# control_board_SMD.net
KiCad netlist of a schematic drawn in EAGLE
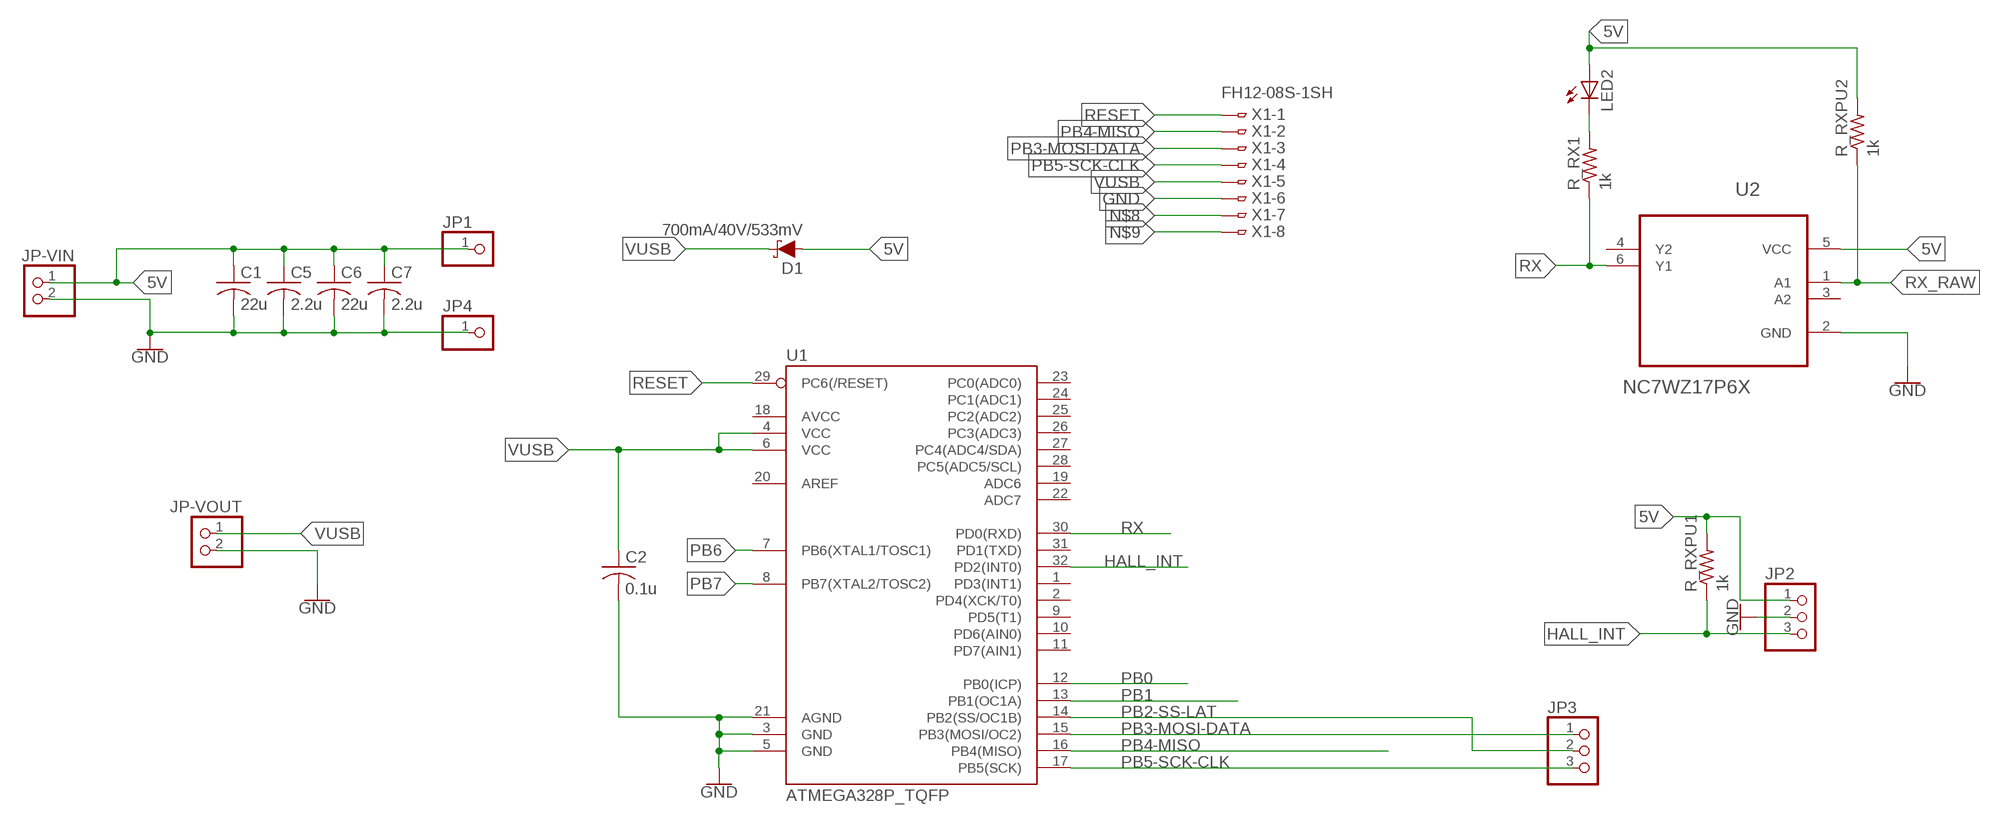
[diagram p0: schematic, sheet 1]

(export (version "E")
  (design (tool "Eeschema 10.0.6"))
  (components
    (comp (ref "C1")
      (value "22u")
      (footprint "eagle-import:C1210")
      (libsource (lib "eagle-import") (part "C-USC1210"))
    )
    (comp (ref "C2")
      (value "0.1u")
      (footprint "eagle-import:C0603")
      (libsource (lib "eagle-import") (part "C-USC0603"))
    )
    (comp (ref "C5")
      (value "2.2u")
      (footprint "eagle-import:C1210")
      (libsource (lib "eagle-import") (part "C-USC1210"))
    )
    (comp (ref "C6")
      (value "22u")
      (footprint "eagle-import:C1210")
      (libsource (lib "eagle-import") (part "C-USC1210"))
    )
    (comp (ref "C7")
      (value "2.2u")
      (footprint "eagle-import:C1210")
      (libsource (lib "eagle-import") (part "C-USC1210"))
    )
    (comp (ref "D1")
      (value "700mA/40V/533mV")
      (footprint "eagle-import:SOT23-3")
      (libsource (lib "eagle-import") (part "DIODE-SCHOTTKY-ZLLS500"))
    )
    (comp (ref "JP-VIN")
      (value "PINHD-1X2")
      (footprint "eagle-import:1X02")
      (libsource (lib "eagle-import") (part "PINHD-1X2"))
    )
    (comp (ref "JP-VOUT")
      (value "PINHD-1X2")
      (footprint "eagle-import:1X02")
      (libsource (lib "eagle-import") (part "PINHD-1X2"))
    )
    (comp (ref "JP1")
      (value "PINHD-1X1")
      (footprint "eagle-import:1X01")
      (libsource (lib "eagle-import") (part "PINHD-1X1"))
    )
    (comp (ref "JP2")
      (value "PINHD-1X3")
      (footprint "eagle-import:1X03")
      (libsource (lib "eagle-import") (part "PINHD-1X3"))
    )
    (comp (ref "JP3")
      (value "PINHD-1X3")
      (footprint "eagle-import:1X03")
      (libsource (lib "eagle-import") (part "PINHD-1X3"))
    )
    (comp (ref "JP4")
      (value "PINHD-1X1")
      (footprint "eagle-import:1X01")
      (libsource (lib "eagle-import") (part "PINHD-1X1"))
    )
    (comp (ref "LED2")
      (value "LEDCHIPLED_0603")
      (footprint "eagle-import:CHIPLED_0603")
      (libsource (lib "eagle-import") (part "LEDCHIPLED_0603"))
    )
    (comp (ref "R_RX1")
      (value "1k")
      (footprint "eagle-import:R0603")
      (libsource (lib "eagle-import") (part "R-US_R0603"))
    )
    (comp (ref "R_RXPU1")
      (value "1k")
      (footprint "eagle-import:R0603")
      (libsource (lib "eagle-import") (part "R-US_R0603"))
    )
    (comp (ref "R_RXPU2")
      (value "1k")
      (footprint "eagle-import:R0603")
      (libsource (lib "eagle-import") (part "R-US_R0603"))
    )
    (comp (ref "U1")
      (value "ATMEGA328P_TQFP")
      (footprint "eagle-import:TQFP32-08")
      (libsource (lib "eagle-import") (part "ATMEGA328P_TQFP"))
    )
    (comp (ref "U2")
      (value "NC7WZ17P6X")
      (footprint "eagle-import:SOT65P210X110-6N")
      (fields (field (name "MF") "Fairchild Semiconductor"))
      (libsource (lib "eagle-import") (part "NC7WZ17P6X"))
    )
    (comp (ref "X1")
      (value "FH12-08S-1SH")
      (footprint "eagle-import:FH12-08S-1SH")
      (libsource (lib "eagle-import") (part "FH12-08S-1SH"))
    )
  )
  (nets
    (net (code "1") (name "/PB0") (class "Default")
      (node (ref "U1") (pin "12") (pinfunction "PB0(ICP)_12") (pintype "bidirectional"))
    )
    (net (code "2") (name "/PB1") (class "Default")
      (node (ref "U1") (pin "13") (pinfunction "PB1(OC1A)_13") (pintype "bidirectional"))
    )
    (net (code "3") (name "/PB2-SS-LAT") (class "Default")
      (node (ref "JP3") (pin "2") (pinfunction "2_2") (pintype "passive"))
      (node (ref "U1") (pin "14") (pinfunction "PB2(SS/OC1B)_14") (pintype "bidirectional"))
    )
    (net (code "4") (name "5V") (class "Default")
      (node (ref "C1") (pin "1") (pinfunction "1_1") (pintype "passive"))
      (node (ref "C5") (pin "1") (pinfunction "1_1") (pintype "passive"))
      (node (ref "C6") (pin "1") (pinfunction "1_1") (pintype "passive"))
      (node (ref "C7") (pin "1") (pinfunction "1_1") (pintype "passive"))
      (node (ref "D1") (pin "1") (pinfunction "A_1") (pintype "passive"))
      (node (ref "JP-VIN") (pin "1") (pinfunction "1_1") (pintype "passive"))
      (node (ref "JP1") (pin "1") (pinfunction "1_1") (pintype "passive"))
      (node (ref "JP2") (pin "1") (pinfunction "1_1") (pintype "passive"))
      (node (ref "LED2") (pin "A") (pinfunction "A_A") (pintype "passive"))
      (node (ref "R_RXPU1") (pin "2") (pinfunction "2_2") (pintype "passive"))
      (node (ref "R_RXPU2") (pin "2") (pinfunction "2_2") (pintype "passive"))
      (node (ref "U2") (pin "5") (pinfunction "VCC_5") (pintype "power_in"))
    )
    (net (code "5") (name "GND") (class "Default")
      (node (ref "C1") (pin "2") (pinfunction "2_2") (pintype "passive"))
      (node (ref "C2") (pin "2") (pinfunction "2_2") (pintype "passive"))
      (node (ref "C5") (pin "2") (pinfunction "2_2") (pintype "passive"))
      (node (ref "C6") (pin "2") (pinfunction "2_2") (pintype "passive"))
      (node (ref "C7") (pin "2") (pinfunction "2_2") (pintype "passive"))
      (node (ref "JP-VIN") (pin "2") (pinfunction "2_2") (pintype "passive"))
      (node (ref "JP-VOUT") (pin "2") (pinfunction "2_2") (pintype "passive"))
      (node (ref "JP2") (pin "2") (pinfunction "2_2") (pintype "passive"))
      (node (ref "JP4") (pin "1") (pinfunction "1_1") (pintype "passive"))
      (node (ref "U1") (pin "21") (pinfunction "AGND_21") (pintype "bidirectional"))
      (node (ref "U1") (pin "3") (pinfunction "GND_3") (pintype "bidirectional"))
      (node (ref "U1") (pin "5") (pinfunction "GND_5") (pintype "bidirectional"))
      (node (ref "U2") (pin "2") (pinfunction "GND_2") (pintype "passive"))
      (node (ref "X1") (pin "6") (pinfunction "1_6") (pintype "passive"))
    )
    (net (code "6") (name "HALL_INT") (class "Default")
      (node (ref "JP2") (pin "3") (pinfunction "3_3") (pintype "passive"))
      (node (ref "R_RXPU1") (pin "1") (pinfunction "1_1") (pintype "passive"))
      (node (ref "U1") (pin "32") (pinfunction "PD2(INT0)_32") (pintype "bidirectional"))
    )
    (net (code "7") (name "N$8") (class "Default")
      (node (ref "X1") (pin "7") (pinfunction "1_7") (pintype "passive"))
    )
    (net (code "8") (name "N$9") (class "Default")
      (node (ref "X1") (pin "8") (pinfunction "1_8") (pintype "passive"))
    )
    (net (code "9") (name "Net-(LED2-PadC)") (class "Default")
      (node (ref "LED2") (pin "C") (pinfunction "C_C") (pintype "passive"))
      (node (ref "R_RX1") (pin "2") (pinfunction "2_2") (pintype "passive"))
    )
    (net (code "10") (name "PB3-MOSI-DATA") (class "Default")
      (node (ref "JP3") (pin "1") (pinfunction "1_1") (pintype "passive"))
      (node (ref "U1") (pin "15") (pinfunction "PB3(MOSI/OC2)_15") (pintype "bidirectional"))
      (node (ref "X1") (pin "3") (pinfunction "1_3") (pintype "passive"))
    )
    (net (code "11") (name "PB4-MISO") (class "Default")
      (node (ref "U1") (pin "16") (pinfunction "PB4(MISO)_16") (pintype "bidirectional"))
      (node (ref "X1") (pin "2") (pinfunction "1_2") (pintype "passive"))
    )
    (net (code "12") (name "PB5-SCK-CLK") (class "Default")
      (node (ref "JP3") (pin "3") (pinfunction "3_3") (pintype "passive"))
      (node (ref "U1") (pin "17") (pinfunction "PB5(SCK)_17") (pintype "bidirectional"))
      (node (ref "X1") (pin "4") (pinfunction "1_4") (pintype "passive"))
    )
    (net (code "13") (name "PB6") (class "Default")
      (node (ref "U1") (pin "7") (pinfunction "PB6(XTAL1/TOSC1)_7") (pintype "bidirectional"))
    )
    (net (code "14") (name "PB7") (class "Default")
      (node (ref "U1") (pin "8") (pinfunction "PB7(XTAL2/TOSC2)_8") (pintype "bidirectional"))
    )
    (net (code "15") (name "RESET") (class "Default")
      (node (ref "U1") (pin "29") (pinfunction "PC6(/RESET)_29") (pintype "bidirectional"))
      (node (ref "X1") (pin "1") (pinfunction "1_1") (pintype "passive"))
    )
    (net (code "16") (name "RX") (class "Default")
      (node (ref "R_RX1") (pin "1") (pinfunction "1_1") (pintype "passive"))
      (node (ref "U1") (pin "30") (pinfunction "PD0(RXD)_30") (pintype "bidirectional"))
      (node (ref "U2") (pin "6") (pinfunction "Y1_6") (pintype "output"))
    )
    (net (code "17") (name "RX_RAW") (class "Default")
      (node (ref "R_RXPU2") (pin "1") (pinfunction "1_1") (pintype "passive"))
      (node (ref "U2") (pin "1") (pinfunction "A1_1") (pintype "input"))
    )
    (net (code "18") (name "VUSB") (class "Default")
      (node (ref "C2") (pin "1") (pinfunction "1_1") (pintype "passive"))
      (node (ref "D1") (pin "3") (pinfunction "C_3") (pintype "passive"))
      (node (ref "JP-VOUT") (pin "1") (pinfunction "1_1") (pintype "passive"))
      (node (ref "U1") (pin "4") (pinfunction "VCC_4") (pintype "bidirectional"))
      (node (ref "U1") (pin "6") (pinfunction "VCC_6") (pintype "bidirectional"))
      (node (ref "X1") (pin "5") (pinfunction "1_5") (pintype "passive"))
    )
    (net (code "19") (name "unconnected-(U1-ADC6-Pad19)") (class "Default")
      (node (ref "U1") (pin "19") (pinfunction "ADC6_19") (pintype "bidirectional"))
    )
    (net (code "20") (name "unconnected-(U1-ADC7-Pad22)") (class "Default")
      (node (ref "U1") (pin "22") (pinfunction "ADC7_22") (pintype "bidirectional"))
    )
    (net (code "21") (name "unconnected-(U1-AREF-Pad20)") (class "Default")
      (node (ref "U1") (pin "20") (pinfunction "AREF_20") (pintype "bidirectional"))
    )
    (net (code "22") (name "unconnected-(U1-AVCC-Pad18)") (class "Default")
      (node (ref "U1") (pin "18") (pinfunction "AVCC_18") (pintype "bidirectional"))
    )
    (net (code "23") (name "unconnected-(U1-PC0(ADC0)-Pad23)") (class "Default")
      (node (ref "U1") (pin "23") (pinfunction "PC0(ADC0)_23") (pintype "bidirectional"))
    )
    (net (code "24") (name "unconnected-(U1-PC1(ADC1)-Pad24)") (class "Default")
      (node (ref "U1") (pin "24") (pinfunction "PC1(ADC1)_24") (pintype "bidirectional"))
    )
    (net (code "25") (name "unconnected-(U1-PC2(ADC2)-Pad25)") (class "Default")
      (node (ref "U1") (pin "25") (pinfunction "PC2(ADC2)_25") (pintype "bidirectional"))
    )
    (net (code "26") (name "unconnected-(U1-PC3(ADC3)-Pad26)") (class "Default")
      (node (ref "U1") (pin "26") (pinfunction "PC3(ADC3)_26") (pintype "bidirectional"))
    )
    (net (code "27") (name "unconnected-(U1-PC4(ADC4{slash}SDA)-Pad27)") (class "Default")
      (node (ref "U1") (pin "27") (pinfunction "PC4(ADC4/SDA)_27") (pintype "bidirectional"))
    )
    (net (code "28") (name "unconnected-(U1-PC5(ADC5{slash}SCL)-Pad28)") (class "Default")
      (node (ref "U1") (pin "28") (pinfunction "PC5(ADC5/SCL)_28") (pintype "bidirectional"))
    )
    (net (code "29") (name "unconnected-(U1-PD1(TXD)-Pad31)") (class "Default")
      (node (ref "U1") (pin "31") (pinfunction "PD1(TXD)_31") (pintype "bidirectional"))
    )
    (net (code "30") (name "unconnected-(U1-PD3(INT1)-Pad1)") (class "Default")
      (node (ref "U1") (pin "1") (pinfunction "PD3(INT1)_1") (pintype "bidirectional"))
    )
    (net (code "31") (name "unconnected-(U1-PD4(XCK{slash}T0)-Pad2)") (class "Default")
      (node (ref "U1") (pin "2") (pinfunction "PD4(XCK/T0)_2") (pintype "bidirectional"))
    )
    (net (code "32") (name "unconnected-(U1-PD5(T1)-Pad9)") (class "Default")
      (node (ref "U1") (pin "9") (pinfunction "PD5(T1)_9") (pintype "bidirectional"))
    )
    (net (code "33") (name "unconnected-(U1-PD6(AIN0)-Pad10)") (class "Default")
      (node (ref "U1") (pin "10") (pinfunction "PD6(AIN0)_10") (pintype "bidirectional"))
    )
    (net (code "34") (name "unconnected-(U1-PD7(AIN1)-Pad11)") (class "Default")
      (node (ref "U1") (pin "11") (pinfunction "PD7(AIN1)_11") (pintype "bidirectional"))
    )
    (net (code "35") (name "unconnected-(U2-A2-Pad3)") (class "Default")
      (node (ref "U2") (pin "3") (pinfunction "A2_3") (pintype "input"))
    )
    (net (code "36") (name "unconnected-(U2-Y2-Pad4)") (class "Default")
      (node (ref "U2") (pin "4") (pinfunction "Y2_4") (pintype "output"))
    )
  )
)
